# WINGS_Componenets.net
KiCad netlist of a schematic drawn in Altium Designer
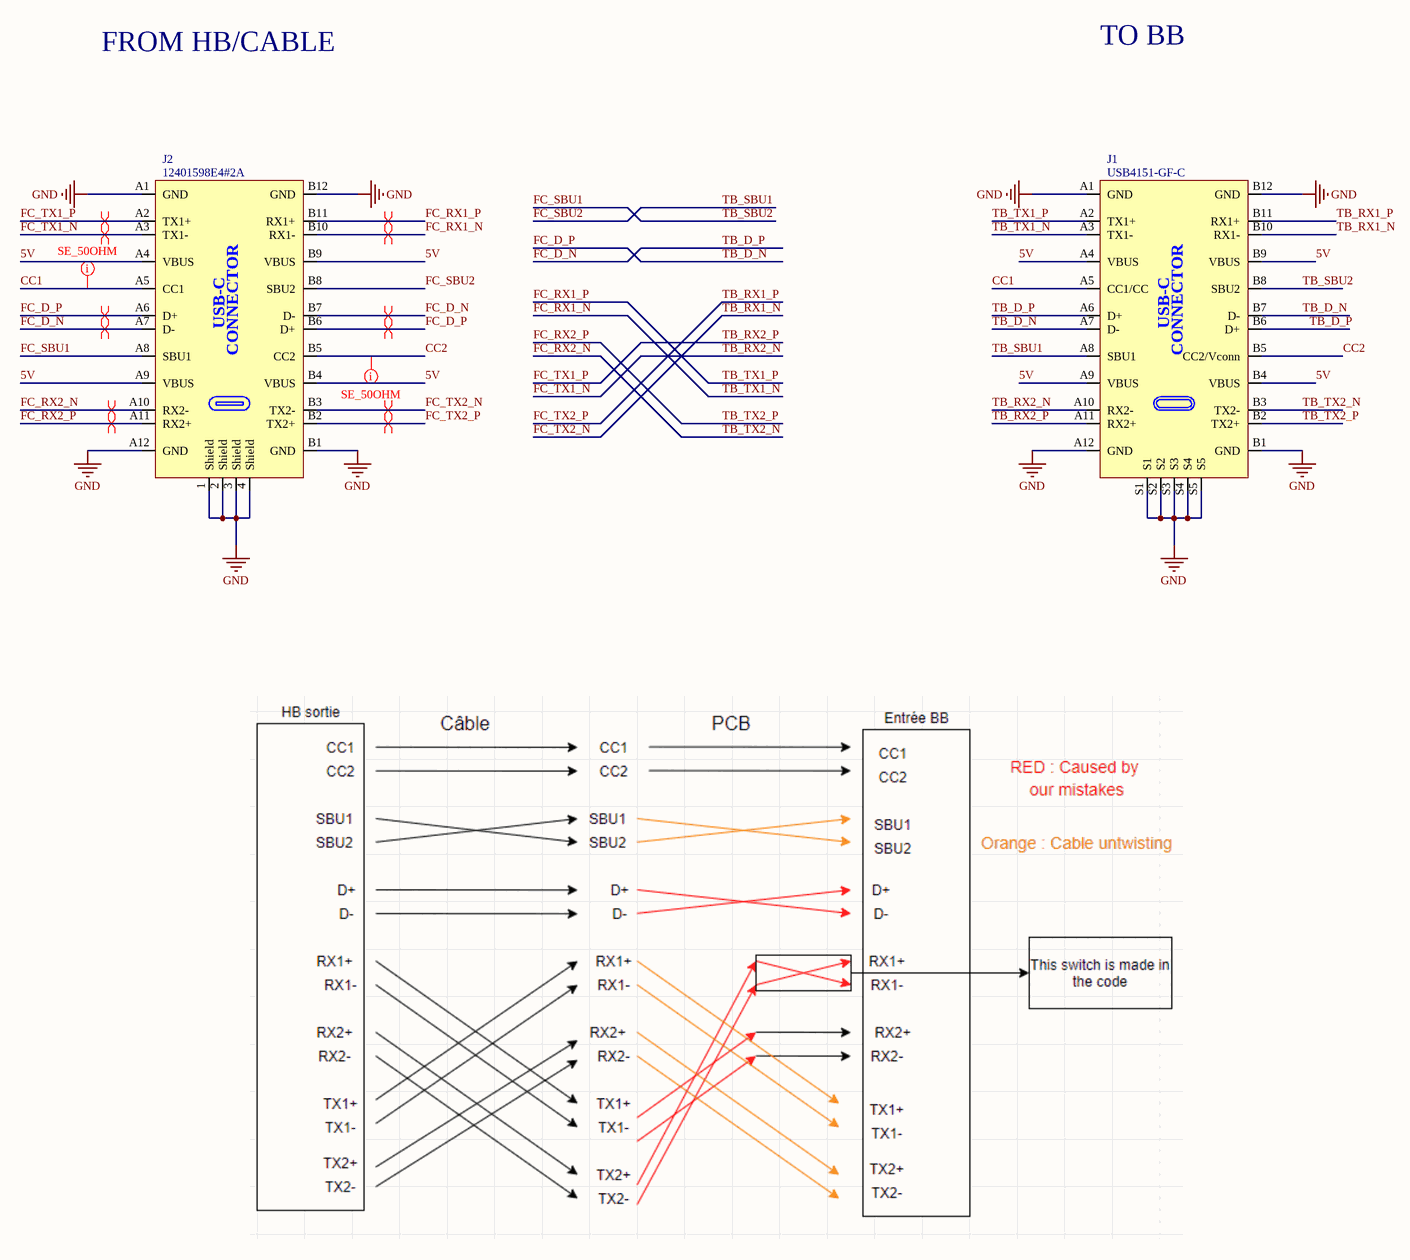
[diagram p0: WINGS_Componenets.SchDoc]

(export (version "E")
  (design (tool "Eeschema 10.0.6"))
  (components
    (comp (ref "J1")
      (value "USB4151-GF-C")
      (footprint "CON_USB-C_USB4151-GF-C")
      (fields
        (field (name "CREATEDBY/DATE") "Philippe Arsenault/2021-08-17")
        (field (name "VERIFIEDBY") "Hubert Dube/2021-09-02")
      )
      (libsource (lib "SWARMUS_LIB") (part "CON_USB_3.2_TypeC_USB4151-GF-C"))
    )
    (comp (ref "J2")
      (value "12401598E4#2A")
      (footprint "CON_USB_3.2_TypeC_12401598E4#2A")
      (description "CON_USB - USB 3.2 Gen 2 (USB 3.1 Gen 2, Superspeed + (USB 3.1)) 24 pos Receptacle - R/A")
      (fields
        (field (name "CREATEDBY/DATE") "Louis-Daniel Gaulin / 07-04-2021")
        (field (name "VERIFIEDBY") "Philippe Arsenault/2021-04-08")
      )
      (libsource (lib "SWARMUS_LIB") (part "CON_USB_3.2_TypeC_12401598E4#2A"))
    )
  )
  (nets
    (net (code "1") (name "/5V") (class "Default")
      (node (ref "J1") (pin "A4") (pinfunction "VBUS_A4") (pintype "passive"))
      (node (ref "J1") (pin "A9") (pinfunction "VBUS_A9") (pintype "passive"))
      (node (ref "J1") (pin "B4") (pinfunction "VBUS_B4") (pintype "passive"))
      (node (ref "J1") (pin "B9") (pinfunction "VBUS_B9") (pintype "passive"))
      (node (ref "J2") (pin "A4") (pinfunction "VBUS_A4") (pintype "passive"))
      (node (ref "J2") (pin "A9") (pinfunction "VBUS_A9") (pintype "passive"))
      (node (ref "J2") (pin "B4") (pinfunction "VBUS_B4") (pintype "passive"))
      (node (ref "J2") (pin "B9") (pinfunction "VBUS_B9") (pintype "passive"))
    )
    (net (code "2") (name "/CC1") (class "Default")
      (node (ref "J1") (pin "A5") (pinfunction "CC1/CC_A5") (pintype "passive"))
      (node (ref "J2") (pin "A5") (pinfunction "CC1_A5") (pintype "passive"))
    )
    (net (code "3") (name "/CC2") (class "Default")
      (node (ref "J1") (pin "B5") (pinfunction "CC2/Vconn_B5") (pintype "passive"))
      (node (ref "J2") (pin "B5") (pinfunction "CC2_B5") (pintype "passive"))
    )
    (net (code "4") (name "/FC_D_N") (class "Default")
      (node (ref "J1") (pin "A6") (pinfunction "D+_A6") (pintype "passive"))
      (node (ref "J1") (pin "B6") (pinfunction "D+_B6") (pintype "passive"))
      (node (ref "J2") (pin "A7") (pinfunction "D-_A7") (pintype "passive"))
      (node (ref "J2") (pin "B7") (pinfunction "D-_B7") (pintype "passive"))
    )
    (net (code "5") (name "/FC_D_P") (class "Default")
      (node (ref "J1") (pin "A7") (pinfunction "D-_A7") (pintype "passive"))
      (node (ref "J1") (pin "B7") (pinfunction "D-_B7") (pintype "passive"))
      (node (ref "J2") (pin "A6") (pinfunction "D+_A6") (pintype "passive"))
      (node (ref "J2") (pin "B6") (pinfunction "D+_B6") (pintype "passive"))
    )
    (net (code "6") (name "/FC_RX1_N") (class "Default")
      (node (ref "J1") (pin "A3") (pinfunction "TX1-_A3") (pintype "passive"))
      (node (ref "J2") (pin "B10") (pinfunction "RX1-_B10") (pintype "passive"))
    )
    (net (code "7") (name "/FC_RX1_P") (class "Default")
      (node (ref "J1") (pin "A2") (pinfunction "TX1+_A2") (pintype "passive"))
      (node (ref "J2") (pin "B11") (pinfunction "RX1+_B11") (pintype "passive"))
    )
    (net (code "8") (name "/FC_RX2_N") (class "Default")
      (node (ref "J1") (pin "B3") (pinfunction "TX2-_B3") (pintype "passive"))
      (node (ref "J2") (pin "A10") (pinfunction "RX2-_A10") (pintype "passive"))
    )
    (net (code "9") (name "/FC_RX2_P") (class "Default")
      (node (ref "J1") (pin "B2") (pinfunction "TX2+_B2") (pintype "passive"))
      (node (ref "J2") (pin "A11") (pinfunction "RX2+_A11") (pintype "passive"))
    )
    (net (code "10") (name "/FC_SBU1") (class "Default")
      (node (ref "J1") (pin "B8") (pinfunction "SBU2_B8") (pintype "passive"))
      (node (ref "J2") (pin "A8") (pinfunction "SBU1_A8") (pintype "passive"))
    )
    (net (code "11") (name "/FC_SBU2") (class "Default")
      (node (ref "J1") (pin "A8") (pinfunction "SBU1_A8") (pintype "passive"))
      (node (ref "J2") (pin "B8") (pinfunction "SBU2_B8") (pintype "passive"))
    )
    (net (code "12") (name "/FC_TX1_N") (class "Default")
      (node (ref "J1") (pin "A10") (pinfunction "RX2-_A10") (pintype "passive"))
      (node (ref "J2") (pin "A3") (pinfunction "TX1-_A3") (pintype "passive"))
    )
    (net (code "13") (name "/FC_TX1_P") (class "Default")
      (node (ref "J1") (pin "A11") (pinfunction "RX2+_A11") (pintype "passive"))
      (node (ref "J2") (pin "A2") (pinfunction "TX1+_A2") (pintype "passive"))
    )
    (net (code "14") (name "/FC_TX2_N") (class "Default")
      (node (ref "J1") (pin "B10") (pinfunction "RX1-_B10") (pintype "passive"))
      (node (ref "J2") (pin "B3") (pinfunction "TX2-_B3") (pintype "passive"))
    )
    (net (code "15") (name "/FC_TX2_P") (class "Default")
      (node (ref "J1") (pin "B11") (pinfunction "RX1+_B11") (pintype "passive"))
      (node (ref "J2") (pin "B2") (pinfunction "TX2+_B2") (pintype "passive"))
    )
    (net (code "16") (name "GND") (class "Default")
      (node (ref "J1") (pin "A1") (pinfunction "GND_A1") (pintype "passive"))
      (node (ref "J1") (pin "A12") (pinfunction "GND_A12") (pintype "passive"))
      (node (ref "J1") (pin "B1") (pinfunction "GND_B1") (pintype "passive"))
      (node (ref "J1") (pin "B12") (pinfunction "GND_B12") (pintype "passive"))
      (node (ref "J1") (pin "S1") (pinfunction "S1_S1") (pintype "passive"))
      (node (ref "J1") (pin "S2") (pinfunction "S2_S2") (pintype "passive"))
      (node (ref "J1") (pin "S3") (pinfunction "S3_S3") (pintype "passive"))
      (node (ref "J1") (pin "S4") (pinfunction "S4_S4") (pintype "passive"))
      (node (ref "J1") (pin "S5") (pinfunction "S5_S5") (pintype "passive"))
      (node (ref "J2") (pin "1") (pinfunction "Shield_1") (pintype "passive"))
      (node (ref "J2") (pin "2") (pinfunction "Shield_2") (pintype "passive"))
      (node (ref "J2") (pin "3") (pinfunction "Shield_3") (pintype "passive"))
      (node (ref "J2") (pin "4") (pinfunction "Shield_4") (pintype "passive"))
      (node (ref "J2") (pin "A1") (pinfunction "GND_A1") (pintype "passive"))
      (node (ref "J2") (pin "A12") (pinfunction "GND_A12") (pintype "passive"))
      (node (ref "J2") (pin "B1") (pinfunction "GND_B1") (pintype "passive"))
      (node (ref "J2") (pin "B12") (pinfunction "GND_B12") (pintype "passive"))
    )
  )
)
